# MUX.net
KiCad netlist of a schematic drawn in Altium Designer
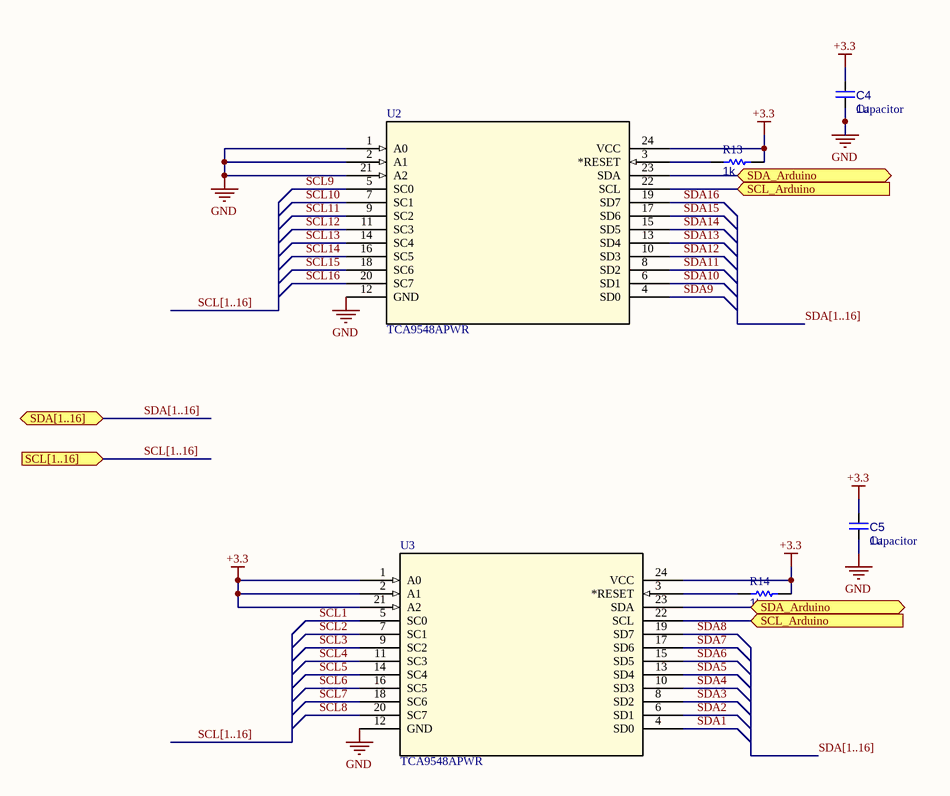
[diagram p0: MUX.SchDoc]

(export (version "E")
  (design (tool "Eeschema 10.0.6"))
  (components
    (comp (ref "C4")
      (value "Capacitor")
      (footprint "C0603B")
      (description "Non-polarized capacitor")
      (fields (field (name "ALTIUM_VALUE") "1u"))
      (libsource (lib "Space Concordia") (part "Capacitor"))
    )
    (comp (ref "C5")
      (value "Capacitor")
      (footprint "C0603B")
      (description "Non-polarized capacitor")
      (fields (field (name "ALTIUM_VALUE") "1u"))
      (libsource (lib "Space Concordia") (part "Capacitor"))
    )
    (comp (ref "R13")
      (value "1k")
      (footprint "R0603B")
      (description "Resistor")
      (libsource (lib "Space Concordia") (part "Resistor"))
    )
    (comp (ref "R14")
      (value "1k")
      (footprint "R0603B")
      (description "Resistor")
      (libsource (lib "Space Concordia") (part "Resistor"))
    )
    (comp (ref "U2")
      (value "TCA9548APWR")
      (footprint "PW24_TEX")
      (description "No Description Available")
      (libsource (lib "Space Concordia") (part "TCA9548APWR"))
    )
    (comp (ref "U3")
      (value "TCA9548APWR")
      (footprint "PW24_TEX")
      (description "No Description Available")
      (libsource (lib "Space Concordia") (part "TCA9548APWR"))
    )
  )
  (nets
    (net (code "1") (name "+3.3") (class "Default")
      (node (ref "C4") (pin "2") (pinfunction "2_2") (pintype "passive"))
      (node (ref "C5") (pin "2") (pinfunction "2_2") (pintype "passive"))
      (node (ref "R13") (pin "2") (pinfunction "2_2") (pintype "passive"))
      (node (ref "R14") (pin "2") (pinfunction "2_2") (pintype "passive"))
      (node (ref "U2") (pin "24") (pinfunction "VCC_24") (pintype "power_in"))
      (node (ref "U3") (pin "1") (pinfunction "A0_1") (pintype "input"))
      (node (ref "U3") (pin "2") (pinfunction "A1_2") (pintype "input"))
      (node (ref "U3") (pin "21") (pinfunction "A2_21") (pintype "input"))
      (node (ref "U3") (pin "24") (pinfunction "VCC_24") (pintype "power_in"))
    )
    (net (code "2") (name "/SCL1") (class "Default")
      (node (ref "U3") (pin "5") (pinfunction "SC0_5") (pintype "passive"))
    )
    (net (code "3") (name "/SCL2") (class "Default")
      (node (ref "U3") (pin "7") (pinfunction "SC1_7") (pintype "passive"))
    )
    (net (code "4") (name "/SCL3") (class "Default")
      (node (ref "U3") (pin "9") (pinfunction "SC2_9") (pintype "passive"))
    )
    (net (code "5") (name "/SCL4") (class "Default")
      (node (ref "U3") (pin "11") (pinfunction "SC3_11") (pintype "passive"))
    )
    (net (code "6") (name "/SCL5") (class "Default")
      (node (ref "U3") (pin "14") (pinfunction "SC4_14") (pintype "passive"))
    )
    (net (code "7") (name "/SCL6") (class "Default")
      (node (ref "U3") (pin "16") (pinfunction "SC5_16") (pintype "passive"))
    )
    (net (code "8") (name "/SCL7") (class "Default")
      (node (ref "U3") (pin "18") (pinfunction "SC6_18") (pintype "passive"))
    )
    (net (code "9") (name "/SCL8") (class "Default")
      (node (ref "U3") (pin "20") (pinfunction "SC7_20") (pintype "passive"))
    )
    (net (code "10") (name "/SCL9") (class "Default")
      (node (ref "U2") (pin "5") (pinfunction "SC0_5") (pintype "passive"))
    )
    (net (code "11") (name "/SCL10") (class "Default")
      (node (ref "U2") (pin "7") (pinfunction "SC1_7") (pintype "passive"))
    )
    (net (code "12") (name "/SCL11") (class "Default")
      (node (ref "U2") (pin "9") (pinfunction "SC2_9") (pintype "passive"))
    )
    (net (code "13") (name "/SCL12") (class "Default")
      (node (ref "U2") (pin "11") (pinfunction "SC3_11") (pintype "passive"))
    )
    (net (code "14") (name "/SCL13") (class "Default")
      (node (ref "U2") (pin "14") (pinfunction "SC4_14") (pintype "passive"))
    )
    (net (code "15") (name "/SCL14") (class "Default")
      (node (ref "U2") (pin "16") (pinfunction "SC5_16") (pintype "passive"))
    )
    (net (code "16") (name "/SCL15") (class "Default")
      (node (ref "U2") (pin "18") (pinfunction "SC6_18") (pintype "passive"))
    )
    (net (code "17") (name "/SCL16") (class "Default")
      (node (ref "U2") (pin "20") (pinfunction "SC7_20") (pintype "passive"))
    )
    (net (code "19") (name "/SCL_Arduino") (class "Default")
      (node (ref "U2") (pin "22") (pinfunction "SCL_22") (pintype "passive"))
      (node (ref "U3") (pin "22") (pinfunction "SCL_22") (pintype "passive"))
    )
    (net (code "20") (name "/SDA1") (class "Default")
      (node (ref "U3") (pin "4") (pinfunction "SD0_4") (pintype "passive"))
    )
    (net (code "21") (name "/SDA2") (class "Default")
      (node (ref "U3") (pin "6") (pinfunction "SD1_6") (pintype "passive"))
    )
    (net (code "22") (name "/SDA3") (class "Default")
      (node (ref "U3") (pin "8") (pinfunction "SD2_8") (pintype "passive"))
    )
    (net (code "23") (name "/SDA4") (class "Default")
      (node (ref "U3") (pin "10") (pinfunction "SD3_10") (pintype "passive"))
    )
    (net (code "24") (name "/SDA5") (class "Default")
      (node (ref "U3") (pin "13") (pinfunction "SD4_13") (pintype "passive"))
    )
    (net (code "25") (name "/SDA6") (class "Default")
      (node (ref "U3") (pin "15") (pinfunction "SD5_15") (pintype "passive"))
    )
    (net (code "26") (name "/SDA7") (class "Default")
      (node (ref "U3") (pin "17") (pinfunction "SD6_17") (pintype "passive"))
    )
    (net (code "27") (name "/SDA8") (class "Default")
      (node (ref "U3") (pin "19") (pinfunction "SD7_19") (pintype "passive"))
    )
    (net (code "28") (name "/SDA9") (class "Default")
      (node (ref "U2") (pin "4") (pinfunction "SD0_4") (pintype "passive"))
    )
    (net (code "29") (name "/SDA10") (class "Default")
      (node (ref "U2") (pin "6") (pinfunction "SD1_6") (pintype "passive"))
    )
    (net (code "30") (name "/SDA11") (class "Default")
      (node (ref "U2") (pin "8") (pinfunction "SD2_8") (pintype "passive"))
    )
    (net (code "31") (name "/SDA12") (class "Default")
      (node (ref "U2") (pin "10") (pinfunction "SD3_10") (pintype "passive"))
    )
    (net (code "32") (name "/SDA13") (class "Default")
      (node (ref "U2") (pin "13") (pinfunction "SD4_13") (pintype "passive"))
    )
    (net (code "33") (name "/SDA14") (class "Default")
      (node (ref "U2") (pin "15") (pinfunction "SD5_15") (pintype "passive"))
    )
    (net (code "34") (name "/SDA15") (class "Default")
      (node (ref "U2") (pin "17") (pinfunction "SD6_17") (pintype "passive"))
    )
    (net (code "35") (name "/SDA16") (class "Default")
      (node (ref "U2") (pin "19") (pinfunction "SD7_19") (pintype "passive"))
    )
    (net (code "37") (name "/SDA_Arduino") (class "Default")
      (node (ref "U2") (pin "23") (pinfunction "SDA_23") (pintype "passive"))
      (node (ref "U3") (pin "23") (pinfunction "SDA_23") (pintype "passive"))
    )
    (net (code "38") (name "GND") (class "Default")
      (node (ref "C4") (pin "1") (pinfunction "1_1") (pintype "passive"))
      (node (ref "C5") (pin "1") (pinfunction "1_1") (pintype "passive"))
      (node (ref "U2") (pin "1") (pinfunction "A0_1") (pintype "input"))
      (node (ref "U2") (pin "12") (pinfunction "GND_12") (pintype "power_in"))
      (node (ref "U2") (pin "2") (pinfunction "A1_2") (pintype "input"))
      (node (ref "U2") (pin "21") (pinfunction "A2_21") (pintype "input"))
      (node (ref "U3") (pin "12") (pinfunction "GND_12") (pintype "power_in"))
    )
    (net (code "39") (name "Net-(U2-*RESET)") (class "Default")
      (node (ref "R13") (pin "1") (pinfunction "1_1") (pintype "passive"))
      (node (ref "U2") (pin "3") (pinfunction "*RESET_3") (pintype "input"))
    )
    (net (code "40") (name "Net-(U3-*RESET)") (class "Default")
      (node (ref "R14") (pin "1") (pinfunction "1_1") (pintype "passive"))
      (node (ref "U3") (pin "3") (pinfunction "*RESET_3") (pintype "input"))
    )
  )
)
